# EEG_photoresistor.net
KiCad netlist of a schematic drawn in Altium Designer
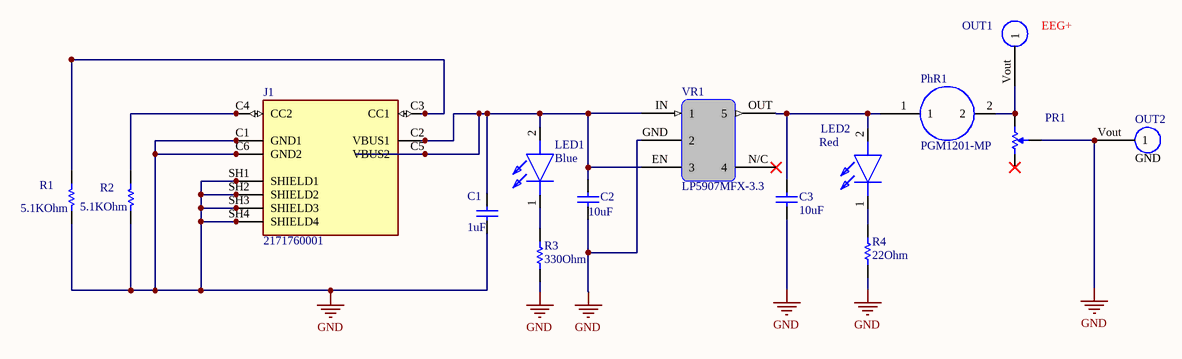
[diagram p0: EEG_photoresistor.SchDoc]

(export (version "E")
  (design (tool "Eeschema 10.0.6"))
  (components
    (comp (ref "C1")
      (value "1uF")
      (footprint "MURA-0805_H_1.35_M")
      (description "CAP, Ceramic, 10 uF, 10%, 10 V, 0805, RoHS, Tape and Reel")
      (fields (field (name "MANUFACTURER") "Murata") (field (name "TOLERANCE") "±10%"))
      (libsource (lib "Altium Content Vault") (part "CAP-NP-2"))
    )
    (comp (ref "C2")
      (value "10uF")
      (footprint "MURA-0805_H_1.35_M")
      (description "CAP, Ceramic, 10 uF, 10%, 10 V, 0805, RoHS, Tape and Reel")
      (fields (field (name "MANUFACTURER") "Murata") (field (name "TOLERANCE") "±10%"))
      (libsource (lib "Altium Content Vault") (part "CAP-NP-2"))
    )
    (comp (ref "C3")
      (value "10uF")
      (footprint "MURA-0805_H_1.35_M")
      (description "CAP, Ceramic, 10 uF, 10%, 10 V, 0805, RoHS, Tape and Reel")
      (fields (field (name "MANUFACTURER") "Murata") (field (name "TOLERANCE") "±10%"))
      (libsource (lib "Altium Content Vault") (part "CAP-NP-2"))
    )
    (comp (ref "J1")
      (value "2171760001")
      (footprint "new")
      (fields (field (name "MF") "Molex"))
      (libsource (lib "2171760001") (part "2171760001"))
    )
    (comp (ref "LED1")
      (value "Blue")
      (footprint "LEDC1005X35N")
      (description "LED")
      (fields
        (field (name "MANUFACTURER_PART_NUMBER") "LTST-C281KGKT")
        (field (name "MOUSER PART NUMBER") "859-LTST-C281KGKT")
      )
      (libsource (lib "SamacSys") (part "LTST-C281KGKT"))
    )
    (comp (ref "LED2")
      (value "Red")
      (footprint "LEDC1005X35N")
      (description "LED")
      (fields
        (field (name "MANUFACTURER_PART_NUMBER") "LTST-C281KGKT")
        (field (name "MOUSER PART NUMBER") "859-LTST-C281KGKT")
      )
      (libsource (lib "SamacSys") (part "LTST-C281KGKT"))
    )
    (comp (ref "OUT1") (value "EEG+") (footprint "VoutPad") (libsource (lib "Vout") (part "Vout")))
    (comp (ref "OUT2") (value "GND") (footprint "VoutPad") (libsource (lib "Vout") (part "Vout")))
    (comp (ref "PhR1")
      (value "PGM1201-MP")
      (footprint "PGM1201-MP")
      (description "Photoresistor; 250mW; 4÷10kΩ; 560nm; THT; 250VDC; ØLED: 12mm")
      (fields (field (name "MANUFACTURER") "Token"))
      (libsource (lib "LDR") (part "PGM1201-MP"))
    )
    (comp (ref "PR1")
      (value "3290W-1-203")
      (footprint "BOUR-3290W")
      (description "Trimming Potentiometer, 20 KOhm, 1 W, -65 to 150 degC, 3-Pin THD, RoHS, Tube")
      (fields (field (name "MANUFACTURER") "Bourns"))
      (libsource (lib "Altium Content Vault") (part "RES-ADJ-3_A"))
    )
    (comp (ref "R1")
      (value "5.1KOhm")
      (footprint "RESC1005X40X25ML05T05")
      (description "Chip Resistor, 330 Ohm, +/- 5%, 100 mW, -55 to 155 degC, 0402 (1005 Metric), RoHS, Tape and Reel")
      (fields (field (name "MANUFACTURER") "Panasonic") (field (name "PART NUMBER") "ERJ-2GEJ331X"))
      (libsource (lib "Altium Content Vault") (part "RES"))
    )
    (comp (ref "R2")
      (value "5.1KOhm")
      (footprint "RESC1005X40X25ML05T05")
      (description "Chip Resistor, 330 Ohm, +/- 5%, 100 mW, -55 to 155 degC, 0402 (1005 Metric), RoHS, Tape and Reel")
      (fields (field (name "MANUFACTURER") "Panasonic") (field (name "PART NUMBER") "ERJ-2GEJ331X"))
      (libsource (lib "Altium Content Vault") (part "RES"))
    )
    (comp (ref "R3")
      (value "330Ohm")
      (footprint "RESC1005X40X25ML05T05")
      (description "Chip Resistor, 330 Ohm, +/- 5%, 100 mW, -55 to 155 degC, 0402 (1005 Metric), RoHS, Tape and Reel")
      (fields (field (name "MANUFACTURER") "Panasonic") (field (name "PART NUMBER") "ERJ-2GEJ331X"))
      (libsource (lib "Altium Content Vault") (part "RES"))
    )
    (comp (ref "R4")
      (value "22Ohm")
      (footprint "RESC1005X40X25ML05T05")
      (description "Chip Resistor, 330 Ohm, +/- 5%, 100 mW, -55 to 155 degC, 0402 (1005 Metric), RoHS, Tape and Reel")
      (fields (field (name "MANUFACTURER") "Panasonic") (field (name "PART NUMBER") "ERJ-2GEJ331X"))
      (libsource (lib "Altium Content Vault") (part "RES"))
    )
    (comp (ref "VR1")
      (value "LP5907MFX-3.3")
      (footprint "LP5907MFX-3.3")
      (description "250-mA Ultra-Low-Noise, Low-IQ LDO")
      (fields
        (field (name "MANUFACTURER PART NUMBER") "LP5907MFX-3.3/NOPB")
        (field (name "MANUFACTURER") "Texas Instruments")
      )
      (libsource (lib "VoltageRegulator") (part "LP5907MFX-3.3"))
    )
  )
  (nets
    (net (code "1") (name "GND") (class "Default")
      (node (ref "C1") (pin "1") (pinfunction "1_1") (pintype "passive"))
      (node (ref "C2") (pin "1") (pinfunction "1_1") (pintype "passive"))
      (node (ref "C3") (pin "1") (pinfunction "1_1") (pintype "passive"))
      (node (ref "J1") (pin "C1") (pinfunction "GND1_C1") (pintype "power_in"))
      (node (ref "J1") (pin "C6") (pinfunction "GND2_C6") (pintype "power_in"))
      (node (ref "J1") (pin "SH1") (pinfunction "SHIELD1_SH1") (pintype "passive"))
      (node (ref "J1") (pin "SH2") (pinfunction "SHIELD2_SH2") (pintype "passive"))
      (node (ref "J1") (pin "SH3") (pinfunction "SHIELD3_SH3") (pintype "passive"))
      (node (ref "J1") (pin "SH4") (pinfunction "SHIELD4_SH4") (pintype "passive"))
      (node (ref "OUT2") (pin "Vout") (pinfunction "1_Vout") (pintype "passive"))
      (node (ref "PR1") (pin "2") (pinfunction "2_2") (pintype "passive"))
      (node (ref "R1") (pin "2") (pinfunction "2_2") (pintype "passive"))
      (node (ref "R2") (pin "1") (pinfunction "1_1") (pintype "passive"))
      (node (ref "R3") (pin "1") (pinfunction "1_1") (pintype "passive"))
      (node (ref "R4") (pin "1") (pinfunction "1_1") (pintype "passive"))
      (node (ref "VR1") (pin "GND") (pinfunction "2_GND") (pintype "passive"))
    )
    (net (code "2") (name "Net-(J1-CC1)") (class "Default")
      (node (ref "J1") (pin "C3") (pinfunction "CC1_C3") (pintype "bidirectional"))
      (node (ref "R1") (pin "1") (pinfunction "1_1") (pintype "passive"))
    )
    (net (code "3") (name "Net-(J1-CC2)") (class "Default")
      (node (ref "J1") (pin "C4") (pinfunction "CC2_C4") (pintype "bidirectional"))
      (node (ref "R2") (pin "2") (pinfunction "2_2") (pintype "passive"))
    )
    (net (code "4") (name "Net-(J1-VBUS1)") (class "Default")
      (node (ref "C1") (pin "2") (pinfunction "2_2") (pintype "passive"))
      (node (ref "C2") (pin "2") (pinfunction "2_2") (pintype "passive"))
      (node (ref "J1") (pin "C2") (pinfunction "VBUS1_C2") (pintype "power_in"))
      (node (ref "J1") (pin "C5") (pinfunction "VBUS2_C5") (pintype "power_in"))
      (node (ref "LED1") (pin "2") (pinfunction "A_2") (pintype "passive"))
      (node (ref "VR1") (pin "EN") (pinfunction "3_EN") (pintype "passive"))
      (node (ref "VR1") (pin "IN") (pinfunction "1_IN") (pintype "input"))
    )
    (net (code "5") (name "Net-(LED1-K)") (class "Default")
      (node (ref "LED1") (pin "1") (pinfunction "K_1") (pintype "passive"))
      (node (ref "R3") (pin "2") (pinfunction "2_2") (pintype "passive"))
    )
    (net (code "6") (name "Net-(LED2-A)") (class "Default")
      (node (ref "C3") (pin "2") (pinfunction "2_2") (pintype "passive"))
      (node (ref "LED2") (pin "2") (pinfunction "A_2") (pintype "passive"))
      (node (ref "PhR1") (pin "1") (pinfunction "1_1") (pintype "passive"))
      (node (ref "VR1") (pin "OUT") (pinfunction "5_OUT") (pintype "output"))
    )
    (net (code "7") (name "Net-(LED2-K)") (class "Default")
      (node (ref "LED2") (pin "1") (pinfunction "K_1") (pintype "passive"))
      (node (ref "R4") (pin "2") (pinfunction "2_2") (pintype "passive"))
    )
    (net (code "8") (name "Net-(OUT1-1)") (class "Default")
      (node (ref "OUT1") (pin "Vout") (pinfunction "1_Vout") (pintype "passive"))
      (node (ref "PR1") (pin "3") (pinfunction "3_3") (pintype "passive"))
      (node (ref "PhR1") (pin "2") (pinfunction "2_2") (pintype "passive"))
    )
    (net (code "9") (name "unconnected-(PR1-Pad1)") (class "Default")
      (node (ref "PR1") (pin "1") (pinfunction "1_1") (pintype "passive+no_connect"))
    )
    (net (code "10") (name "unconnected-(VR1-4-PadN{slash}C)") (class "Default")
      (node (ref "VR1") (pin "N/C") (pinfunction "4_N/C") (pintype "passive+no_connect"))
    )
  )
)
